# PDOC.net
KiCad netlist of a schematic drawn in Altium Designer
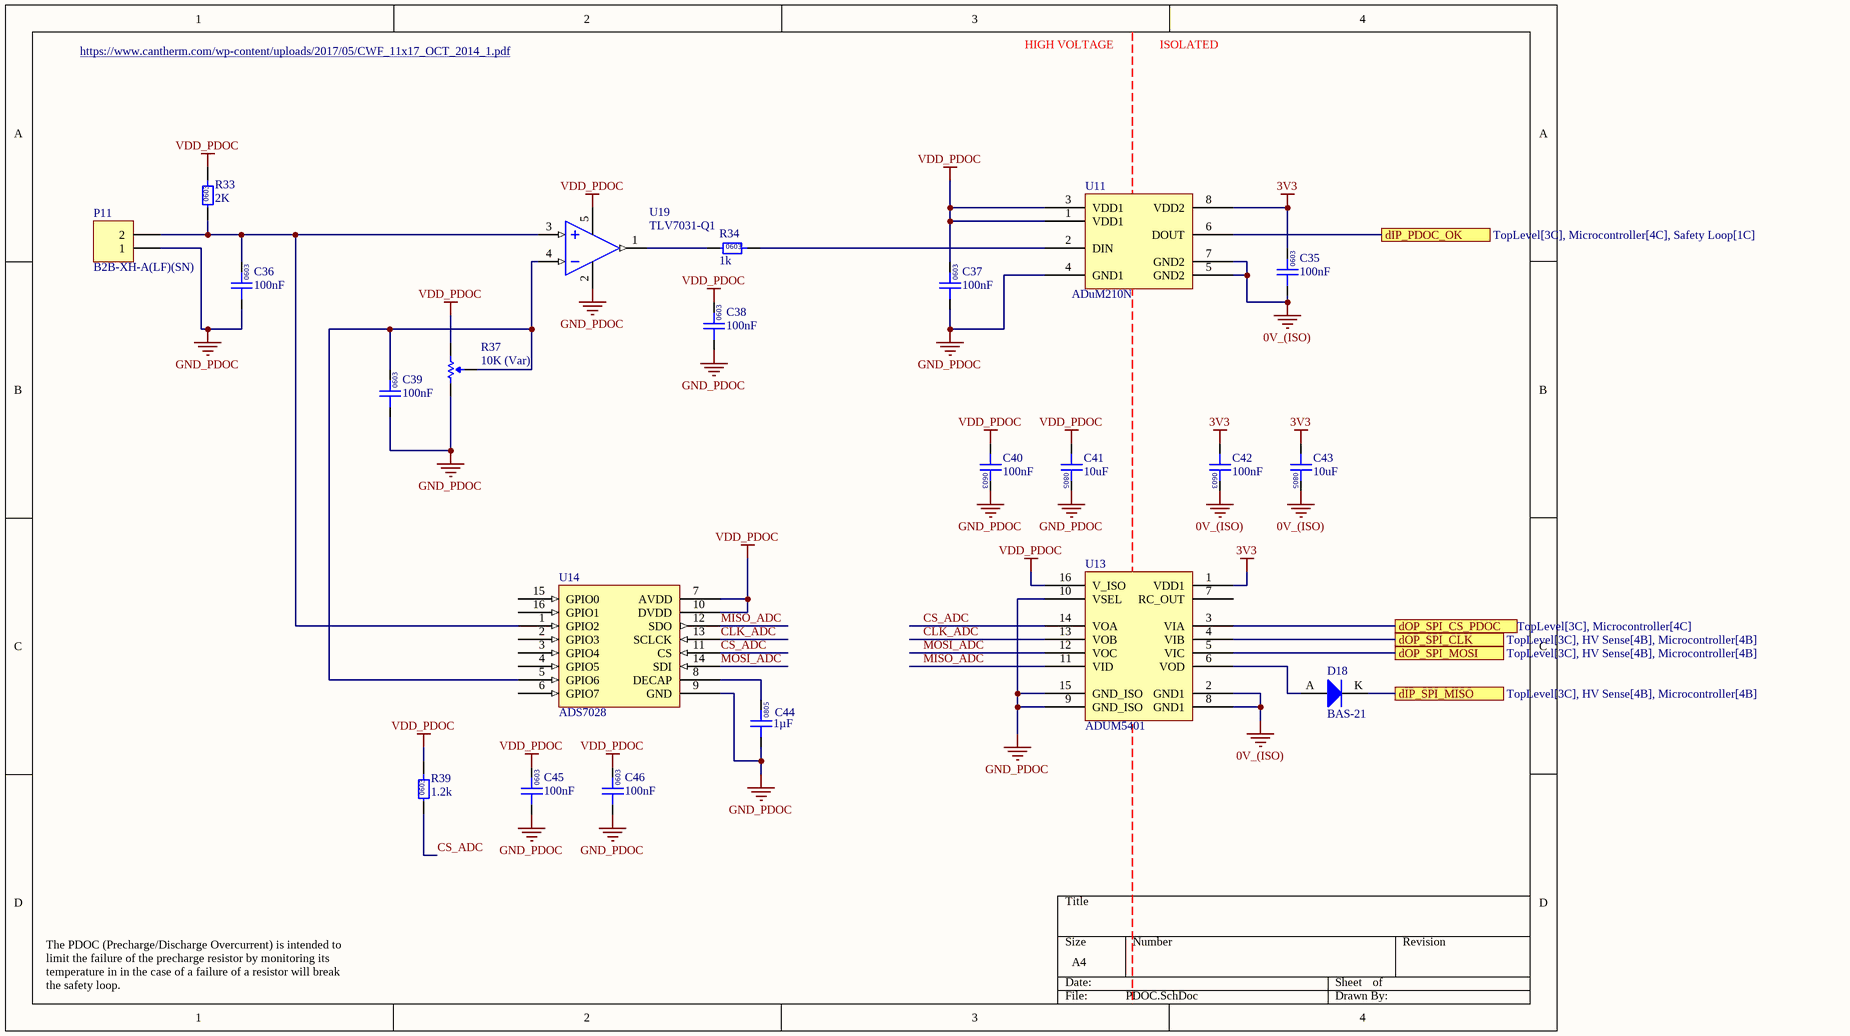
[diagram p0: PDOC.SchDoc]

(export (version "E")
  (design (tool "Eeschema 10.0.6"))
  (components
    (comp (ref "C35")
      (value "100nF")
      (footprint "0603")
      (fields
        (field (name "PART NUMBER") "GCM188L81H104KA57D")
        (field (name "MANUFACTURER") "muRata")
        (field (name "TOLERANCE") "±10%")
      )
      (libsource (lib "ts_standard_library") (part "Capacitor 0603"))
    )
    (comp (ref "C36")
      (value "100nF")
      (footprint "0603")
      (fields
        (field (name "PART NUMBER") "GCM188L81H104KA57D")
        (field (name "MANUFACTURER") "muRata")
        (field (name "TOLERANCE") "±10%")
      )
      (libsource (lib "ts_standard_library") (part "Capacitor 0603"))
    )
    (comp (ref "C37")
      (value "100nF")
      (footprint "0603")
      (fields
        (field (name "PART NUMBER") "GCM188L81H104KA57D")
        (field (name "MANUFACTURER") "muRata")
        (field (name "TOLERANCE") "±10%")
      )
      (libsource (lib "ts_standard_library") (part "Capacitor 0603"))
    )
    (comp (ref "C38")
      (value "100nF")
      (footprint "0603")
      (fields
        (field (name "PART NUMBER") "GCM188L81H104KA57D")
        (field (name "MANUFACTURER") "muRata")
        (field (name "TOLERANCE") "±10%")
      )
      (libsource (lib "ts_standard_library") (part "Capacitor 0603"))
    )
    (comp (ref "C39")
      (value "100nF")
      (footprint "0603")
      (fields
        (field (name "PART NUMBER") "GCM188L81H104KA57D")
        (field (name "MANUFACTURER") "muRata")
        (field (name "TOLERANCE") "±10%")
      )
      (libsource (lib "ts_standard_library") (part "Capacitor 0603"))
    )
    (comp (ref "C40")
      (value "100nF")
      (footprint "0603")
      (fields
        (field (name "PART NUMBER") "GCM188L81H104KA57D")
        (field (name "MANUFACTURER") "muRata")
        (field (name "TOLERANCE") "±10%")
      )
      (libsource (lib "ts_standard_library") (part "Capacitor 0603"))
    )
    (comp (ref "C41")
      (value "10uF")
      (footprint "0805")
      (fields
        (field (name "PART NUMBER") "GRM21BR6YA106KE43L")
        (field (name "MANUFACTURER") "muRata")
        (field (name "TOLERANCE") "10%")
      )
      (libsource (lib "ts_standard_library") (part "Capacitor 0805"))
    )
    (comp (ref "C42")
      (value "100nF")
      (footprint "0603")
      (fields
        (field (name "PART NUMBER") "GCM188L81H104KA57D")
        (field (name "MANUFACTURER") "muRata")
        (field (name "TOLERANCE") "±10%")
      )
      (libsource (lib "ts_standard_library") (part "Capacitor 0603"))
    )
    (comp (ref "C43")
      (value "10uF")
      (footprint "0805")
      (fields
        (field (name "PART NUMBER") "GRM21BR6YA106KE43L")
        (field (name "MANUFACTURER") "muRata")
        (field (name "TOLERANCE") "10%")
      )
      (libsource (lib "ts_standard_library") (part "Capacitor 0805"))
    )
    (comp (ref "C44")
      (value "1µF")
      (footprint "0805")
      (fields
        (field (name "PART NUMBER") "GCM21BR71H105KA03L")
        (field (name "MANUFACTURER") "muRata")
        (field (name "TOLERANCE") "±10%")
      )
      (libsource (lib "ts_standard_library") (part "Capacitor 0805"))
    )
    (comp (ref "C45")
      (value "100nF")
      (footprint "0603")
      (fields
        (field (name "PART NUMBER") "GCM188L81H104KA57D")
        (field (name "MANUFACTURER") "muRata")
        (field (name "TOLERANCE") "±10%")
      )
      (libsource (lib "ts_standard_library") (part "Capacitor 0603"))
    )
    (comp (ref "C46")
      (value "100nF")
      (footprint "0603")
      (fields
        (field (name "PART NUMBER") "GCM188L81H104KA57D")
        (field (name "MANUFACTURER") "muRata")
        (field (name "TOLERANCE") "±10%")
      )
      (libsource (lib "ts_standard_library") (part "Capacitor 0603"))
    )
    (comp (ref "D18")
      (value "BAS-21")
      (footprint "NEXPERIA_SOT23")
      (fields (field (name "MANUFACTURER") "Nexperia USA Inc."))
      (libsource (lib "ts_standard_library") (part "Diode"))
    )
    (comp (ref "P11")
      (value "B2B-XH-A(LF)(SN)")
      (footprint "XH 2 PIN VERT")
      (fields (field (name "DIGIKEY PART NUMBER") "455-2247-ND") (field (name "CONTACT") "Tin"))
      (libsource (lib "ts_standard_connectors") (part "Header 1x2"))
    )
    (comp (ref "R33")
      (value "2K")
      (footprint "0603")
      (fields
        (field (name "PART NUMBER") "RC0603FR-072KL")
        (field (name "MANUFACTURER") "YAGEO")
        (field (name "TOLERANCE") "0.01")
      )
      (libsource (lib "ts_standard_library") (part "Resistor 0603"))
    )
    (comp (ref "R34")
      (value "1k")
      (footprint "0603")
      (fields
        (field (name "PART NUMBER") "RC0603FR-071KL")
        (field (name "MANUFACTURER") "YAGEO")
        (field (name "TOLERANCE") "0.01")
      )
      (libsource (lib "ts_standard_library") (part "Resistor 0603"))
    )
    (comp (ref "R37")
      (value "10K (Var)")
      (footprint "B 3296")
      (fields
        (field (name "PART NUMBER") "3296W-1-103LF")
        (field (name "MANUFACTURER") "Bournes Inc")
        (field (name "TOLERANCE") "0.1")
      )
      (libsource (lib "ts_standard_library") (part "Resistor (Potentiometer)"))
    )
    (comp (ref "R39")
      (value "1.2k")
      (footprint "0603")
      (fields
        (field (name "PART NUMBER") "RC0603JR-071K2L")
        (field (name "MANUFACTURER") "YAGEO")
        (field (name "TOLERANCE") "0.01")
      )
      (libsource (lib "ts_standard_library") (part "Resistor 0603"))
    )
    (comp (ref "U11")
      (value "ADuM210N")
      (footprint "SOIC-8W")
      (description "DIGITAL ISOLATOR, SINGLE CHANNEL")
      (libsource (lib "Team Swinburne") (part "ADuM210N"))
    )
    (comp (ref "U13")
      (value "ADUM5401")
      (footprint "AD 16-SOIC")
      (description "Quad Channel 2.5kV Digital Isolator with isoPower")
      (fields (field (name "MANUFACTURER") "Analogue Devices"))
      (libsource (lib "ts_standard_library") (part "ADUM5401"))
    )
    (comp (ref "U14")
      (value "ADS7028")
      (footprint "WFQN-16")
      (description "IC ADC 12BIT SAR 16WQFN")
      (fields (field (name "PART NUMBER") "ADS7028IRTER") (field (name "MANUFACTURER") "Texas Instruments"))
      (libsource (lib "ts_standard_library") (part "ADS7028IRTER"))
    )
    (comp (ref "U19")
      (value "TLV7031-Q1")
      (footprint "TI SOT-23-5")
      (fields
        (field (name "MANUFACTURER") "Texas Instruments")
        (field (name "DIGIKEY PART NUMBER") "296-TLV7031QDBVRQ1CT-ND")
      )
      (libsource (lib "ts_standard_library") (part "TLV7031-Q1"))
    )
  )
  (nets
    (net (code "1") (name "/CLK_ADC") (class "Default")
      (node (ref "U13") (pin "13") (pinfunction "VOB_13") (pintype "passive"))
      (node (ref "U14") (pin "13") (pinfunction "SCLCK_13") (pintype "input"))
    )
    (net (code "2") (name "/CS_ADC") (class "Default")
      (node (ref "R39") (pin "1") (pinfunction "1_1") (pintype "passive"))
      (node (ref "U13") (pin "14") (pinfunction "VOA_14") (pintype "passive"))
      (node (ref "U14") (pin "11") (pinfunction "CS_11") (pintype "input"))
    )
    (net (code "3") (name "/MISO_ADC") (class "Default")
      (node (ref "U13") (pin "11") (pinfunction "VID_11") (pintype "passive"))
      (node (ref "U14") (pin "12") (pinfunction "SDO_12") (pintype "output"))
    )
    (net (code "4") (name "/MOSI_ADC") (class "Default")
      (node (ref "U13") (pin "12") (pinfunction "VOC_12") (pintype "passive"))
      (node (ref "U14") (pin "14") (pinfunction "SDI_14") (pintype "input"))
    )
    (net (code "5") (name "/dIP_PDOC_OK") (class "Default")
      (node (ref "U11") (pin "6") (pinfunction "DOUT_6") (pintype "passive"))
    )
    (net (code "6") (name "/dIP_SPI_MISO") (class "Default")
      (node (ref "D18") (pin "K") (pinfunction "K_K") (pintype "passive"))
    )
    (net (code "7") (name "/dOP_SPI_CLK") (class "Default")
      (node (ref "U13") (pin "4") (pinfunction "VIB_4") (pintype "passive"))
    )
    (net (code "8") (name "/dOP_SPI_CS_PDOC") (class "Default")
      (node (ref "U13") (pin "3") (pinfunction "VIA_3") (pintype "passive"))
    )
    (net (code "9") (name "/dOP_SPI_MOSI") (class "Default")
      (node (ref "U13") (pin "5") (pinfunction "VIC_5") (pintype "passive"))
    )
    (net (code "10") (name "0V_(ISO)") (class "Default")
      (node (ref "C35") (pin "1") (pinfunction "1_1") (pintype "passive"))
      (node (ref "C42") (pin "2") (pinfunction "2_2") (pintype "passive"))
      (node (ref "C43") (pin "2") (pinfunction "2_2") (pintype "passive"))
      (node (ref "U11") (pin "5") (pinfunction "GND2_5") (pintype "passive"))
      (node (ref "U11") (pin "7") (pinfunction "GND2_7") (pintype "passive"))
      (node (ref "U13") (pin "2") (pinfunction "GND1_2") (pintype "passive"))
      (node (ref "U13") (pin "8") (pinfunction "GND1_8") (pintype "passive"))
    )
    (net (code "11") (name "3V3") (class "Default")
      (node (ref "C35") (pin "2") (pinfunction "2_2") (pintype "passive"))
      (node (ref "C42") (pin "1") (pinfunction "1_1") (pintype "passive"))
      (node (ref "C43") (pin "1") (pinfunction "1_1") (pintype "passive"))
      (node (ref "U11") (pin "8") (pinfunction "VDD2_8") (pintype "passive"))
      (node (ref "U13") (pin "1") (pinfunction "VDD1_1") (pintype "passive"))
    )
    (net (code "12") (name "GND_PDOC") (class "Default")
      (node (ref "C36") (pin "1") (pinfunction "1_1") (pintype "passive"))
      (node (ref "C37") (pin "1") (pinfunction "1_1") (pintype "passive"))
      (node (ref "C38") (pin "1") (pinfunction "1_1") (pintype "passive"))
      (node (ref "C39") (pin "1") (pinfunction "1_1") (pintype "passive"))
      (node (ref "C40") (pin "2") (pinfunction "2_2") (pintype "passive"))
      (node (ref "C41") (pin "2") (pinfunction "2_2") (pintype "passive"))
      (node (ref "C44") (pin "1") (pinfunction "1_1") (pintype "passive"))
      (node (ref "C45") (pin "1") (pinfunction "1_1") (pintype "passive"))
      (node (ref "C46") (pin "1") (pinfunction "1_1") (pintype "passive"))
      (node (ref "P11") (pin "1") (pinfunction "1_1") (pintype "passive"))
      (node (ref "R37") (pin "3") (pinfunction "CW_3") (pintype "passive"))
      (node (ref "U11") (pin "4") (pinfunction "GND1_4") (pintype "passive"))
      (node (ref "U13") (pin "10") (pinfunction "VSEL_10") (pintype "passive"))
      (node (ref "U13") (pin "15") (pinfunction "GND_ISO_15") (pintype "passive"))
      (node (ref "U13") (pin "9") (pinfunction "GND_ISO_9") (pintype "passive"))
      (node (ref "U14") (pin "9") (pinfunction "GND_9") (pintype "power_in"))
      (node (ref "U19") (pin "2") (pinfunction "V-_2") (pintype "power_in"))
    )
    (net (code "13") (name "Net-(R37-Wiper)") (class "Default")
      (node (ref "C39") (pin "2") (pinfunction "2_2") (pintype "passive"))
      (node (ref "R37") (pin "2") (pinfunction "Wiper_2") (pintype "passive"))
      (node (ref "U14") (pin "5") (pinfunction "GPIO6_5") (pintype "input"))
      (node (ref "U19") (pin "4") (pinfunction "IN-_4") (pintype "input"))
    )
    (net (code "14") (name "Net-(U11-DIN)") (class "Default")
      (node (ref "R34") (pin "2") (pinfunction "2_2") (pintype "passive"))
      (node (ref "U11") (pin "2") (pinfunction "DIN_2") (pintype "passive"))
    )
    (net (code "15") (name "Net-(U13-VOD)") (class "Default")
      (node (ref "D18") (pin "A") (pinfunction "A_A") (pintype "passive"))
      (node (ref "U13") (pin "6") (pinfunction "VOD_6") (pintype "passive"))
    )
    (net (code "16") (name "Net-(U14-DECAP)") (class "Default")
      (node (ref "C44") (pin "2") (pinfunction "2_2") (pintype "passive"))
      (node (ref "U14") (pin "8") (pinfunction "DECAP_8") (pintype "power_in"))
    )
    (net (code "17") (name "Net-(U14-GPIO2)") (class "Default")
      (node (ref "C36") (pin "2") (pinfunction "2_2") (pintype "passive"))
      (node (ref "P11") (pin "2") (pinfunction "2_2") (pintype "passive"))
      (node (ref "R33") (pin "1") (pinfunction "1_1") (pintype "passive"))
      (node (ref "U14") (pin "1") (pinfunction "GPIO2_1") (pintype "input"))
      (node (ref "U19") (pin "3") (pinfunction "IN+_3") (pintype "input"))
    )
    (net (code "18") (name "Net-(U19-OUT)") (class "Default")
      (node (ref "R34") (pin "1") (pinfunction "1_1") (pintype "passive"))
      (node (ref "U19") (pin "1") (pinfunction "OUT_1") (pintype "output"))
    )
    (net (code "19") (name "VDD_PDOC") (class "Default")
      (node (ref "C37") (pin "2") (pinfunction "2_2") (pintype "passive"))
      (node (ref "C38") (pin "2") (pinfunction "2_2") (pintype "passive"))
      (node (ref "C40") (pin "1") (pinfunction "1_1") (pintype "passive"))
      (node (ref "C41") (pin "1") (pinfunction "1_1") (pintype "passive"))
      (node (ref "C45") (pin "2") (pinfunction "2_2") (pintype "passive"))
      (node (ref "C46") (pin "2") (pinfunction "2_2") (pintype "passive"))
      (node (ref "R33") (pin "2") (pinfunction "2_2") (pintype "passive"))
      (node (ref "R37") (pin "1") (pinfunction "CCW_1") (pintype "passive"))
      (node (ref "R39") (pin "2") (pinfunction "2_2") (pintype "passive"))
      (node (ref "U11") (pin "1") (pinfunction "VDD1_1") (pintype "passive"))
      (node (ref "U11") (pin "3") (pinfunction "VDD1_3") (pintype "passive"))
      (node (ref "U13") (pin "16") (pinfunction "V_ISO_16") (pintype "passive"))
      (node (ref "U14") (pin "10") (pinfunction "DVDD_10") (pintype "power_in"))
      (node (ref "U14") (pin "7") (pinfunction "AVDD_7") (pintype "power_in"))
      (node (ref "U19") (pin "5") (pinfunction "Vcc_5") (pintype "power_in"))
    )
    (net (code "20") (name "unconnected-(U13-RC_OUT-Pad7)") (class "Default")
      (node (ref "U13") (pin "7") (pinfunction "RC_OUT_7") (pintype "passive"))
    )
    (net (code "21") (name "unconnected-(U14-GPIO0-Pad15)") (class "Default")
      (node (ref "U14") (pin "15") (pinfunction "GPIO0_15") (pintype "input"))
    )
    (net (code "22") (name "unconnected-(U14-GPIO1-Pad16)") (class "Default")
      (node (ref "U14") (pin "16") (pinfunction "GPIO1_16") (pintype "input"))
    )
    (net (code "23") (name "unconnected-(U14-GPIO3-Pad2)") (class "Default")
      (node (ref "U14") (pin "2") (pinfunction "GPIO3_2") (pintype "input"))
    )
    (net (code "24") (name "unconnected-(U14-GPIO4-Pad3)") (class "Default")
      (node (ref "U14") (pin "3") (pinfunction "GPIO4_3") (pintype "input"))
    )
    (net (code "25") (name "unconnected-(U14-GPIO5-Pad4)") (class "Default")
      (node (ref "U14") (pin "4") (pinfunction "GPIO5_4") (pintype "input"))
    )
    (net (code "26") (name "unconnected-(U14-GPIO7-Pad6)") (class "Default")
      (node (ref "U14") (pin "6") (pinfunction "GPIO7_6") (pintype "input"))
    )
  )
)
